# design.net
KiCad netlist of a schematic drawn in Altium Designer
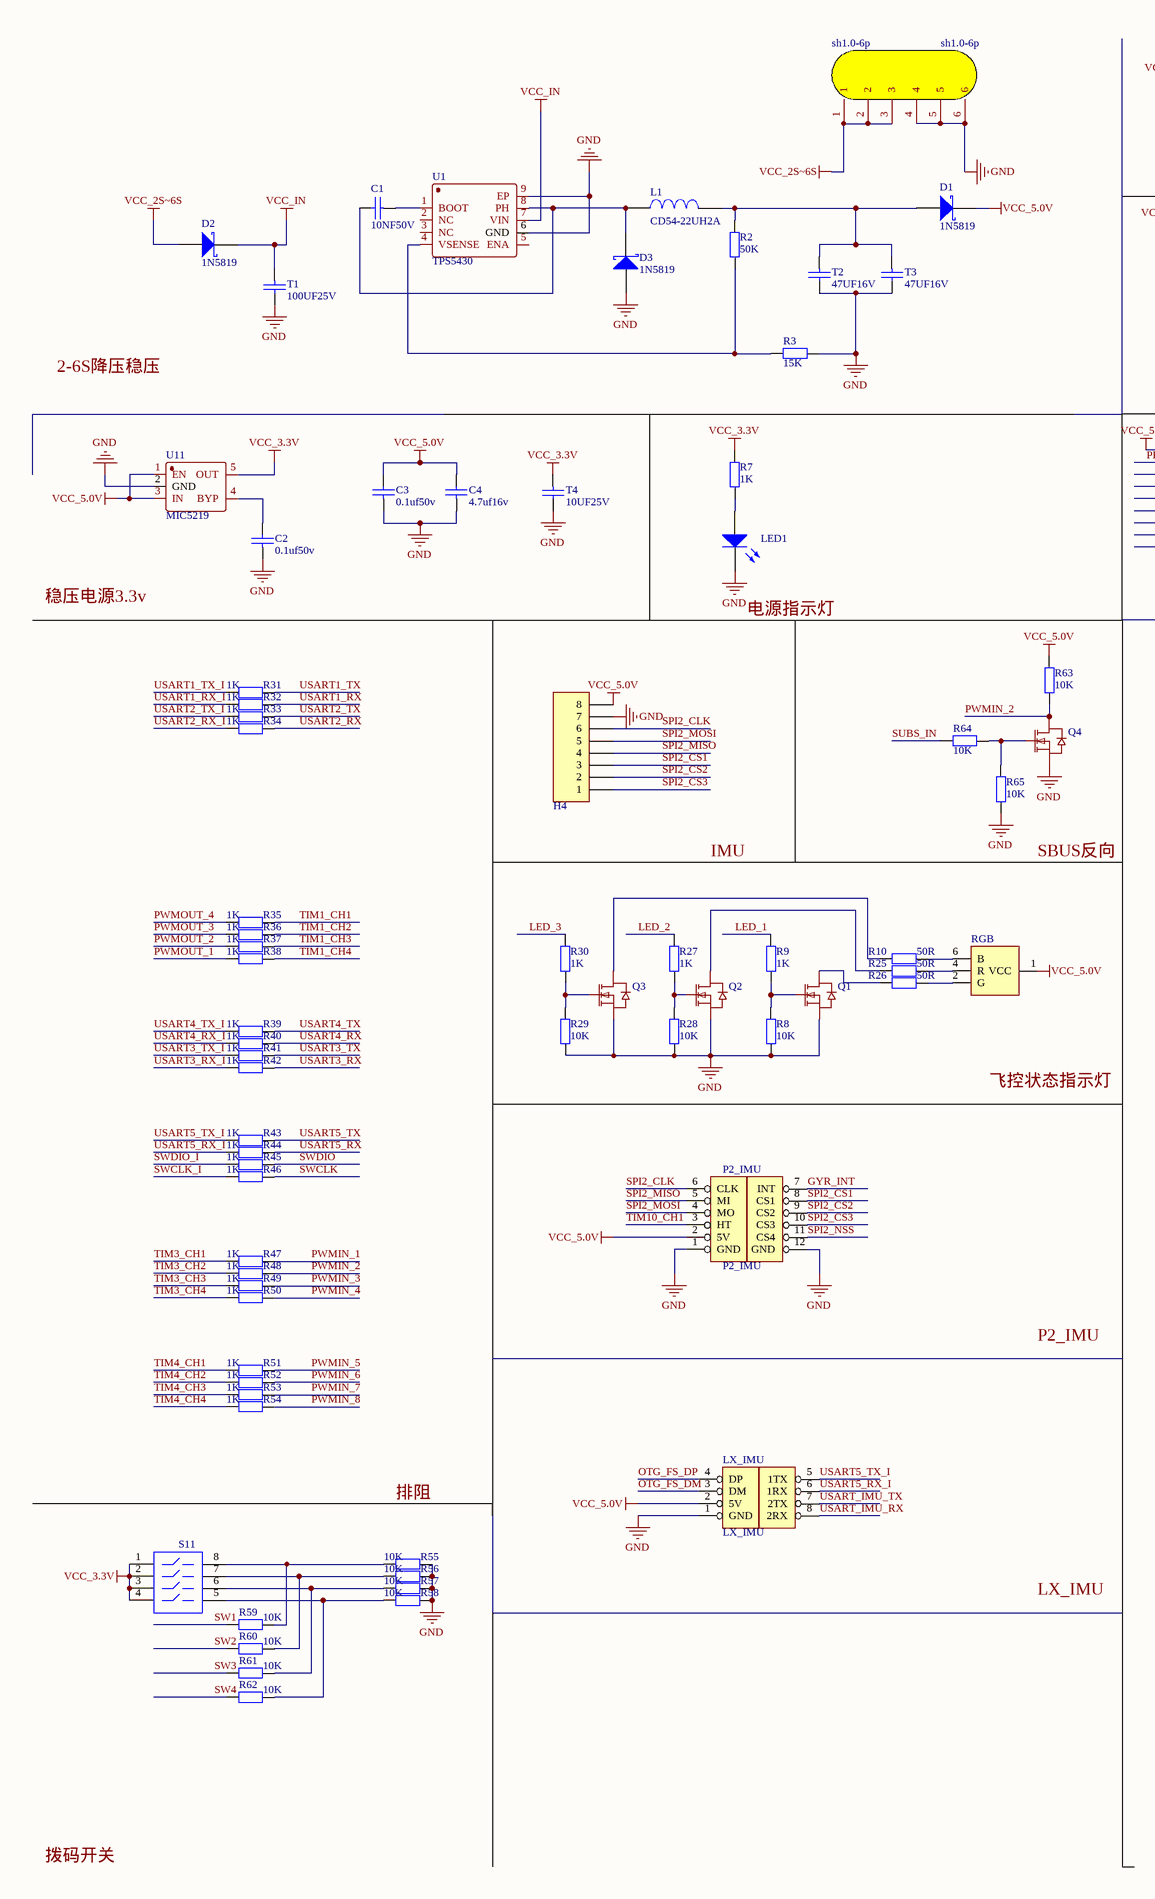
[diagram p0: 飞控板.SchDoc, left]
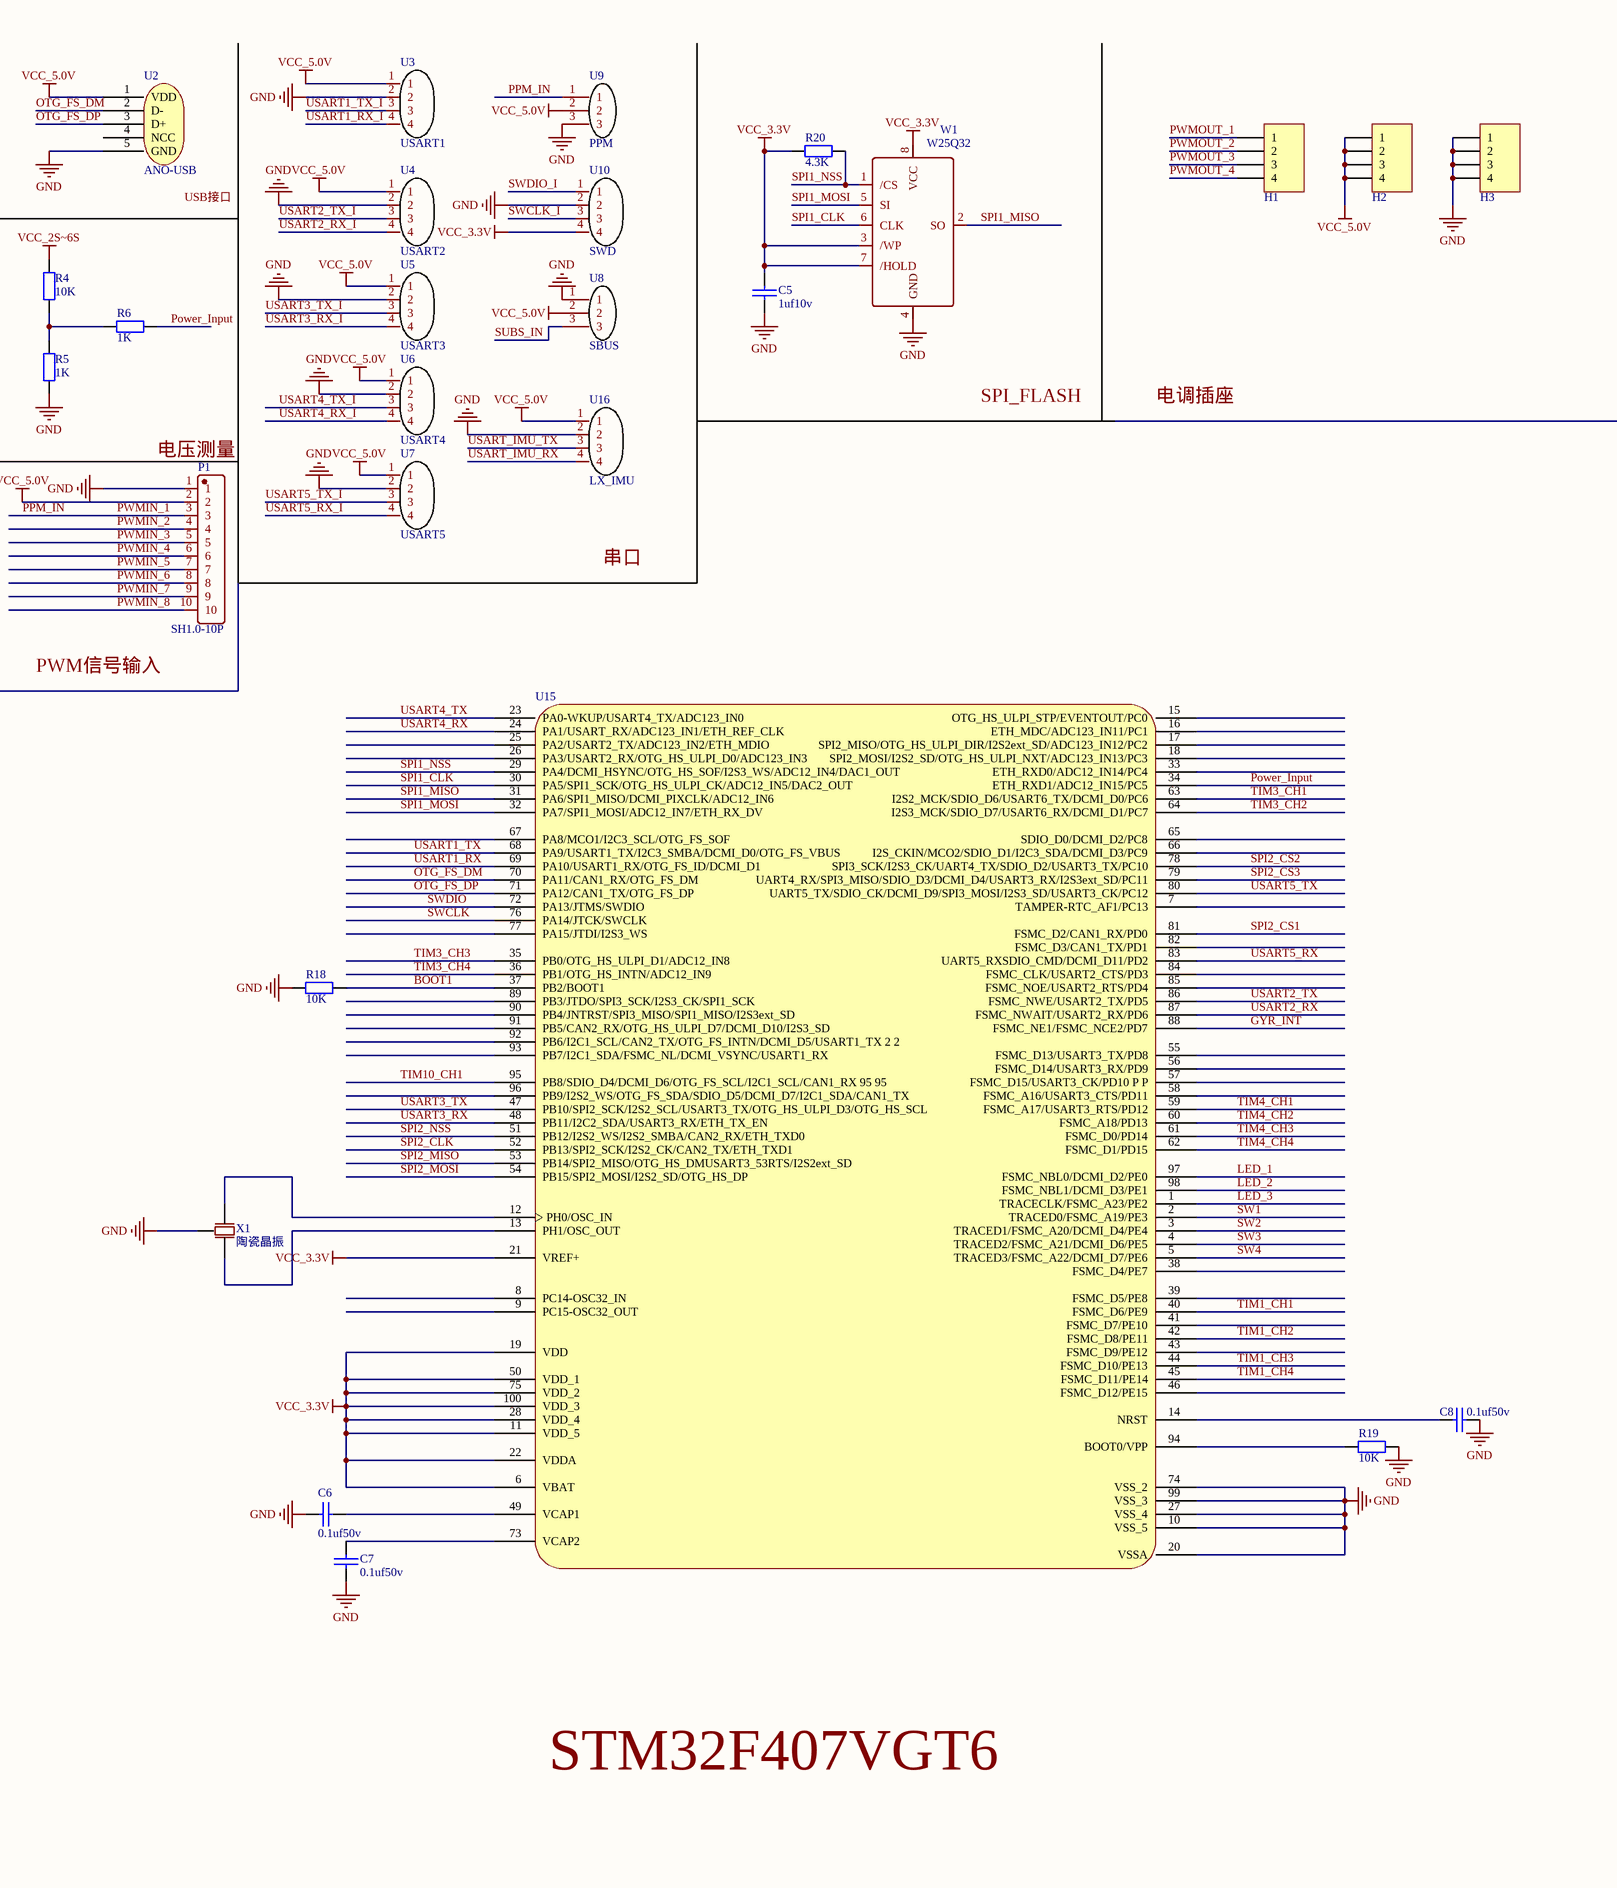
[diagram p1: 飞控板.SchDoc, right]

(export (version "E")
  (design (tool "Eeschema 10.0.6"))
  (components
    (comp (ref "C1")
      (value "10NF50V")
      (footprint "0805C")
      (description "无极性电容")
      (libsource (lib "电容") (part "CAP"))
    )
    (comp (ref "C2")
      (value "0.1uf50v")
      (footprint "0805C")
      (description "无极性电容")
      (libsource (lib "电容") (part "CAP"))
    )
    (comp (ref "C3")
      (value "0.1uf50v")
      (footprint "0805C")
      (description "无极性电容")
      (libsource (lib "电容") (part "CAP"))
    )
    (comp (ref "C4")
      (value "4.7uf16v")
      (footprint "0805C")
      (description "无极性电容")
      (libsource (lib "电容") (part "CAP"))
    )
    (comp (ref "C5")
      (value "1uf10v")
      (footprint "0805C")
      (description "无极性电容")
      (libsource (lib "电容") (part "CAP"))
    )
    (comp (ref "C6")
      (value "0.1uf50v")
      (footprint "0805C")
      (description "无极性电容")
      (libsource (lib "电容") (part "CAP"))
    )
    (comp (ref "C7")
      (value "0.1uf50v")
      (footprint "0805C")
      (description "无极性电容")
      (libsource (lib "电容") (part "CAP"))
    )
    (comp (ref "C8")
      (value "0.1uf50v")
      (footprint "0805C")
      (description "无极性电容")
      (libsource (lib "电容") (part "CAP"))
    )
    (comp (ref "D1")
      (value "1N5819")
      (footprint "DO214AC_SMA")
      (description "贴片肖特基二极管")
      (libsource (lib "1.二极管") (part "1N5817-5819SMD"))
    )
    (comp (ref "D2")
      (value "1N5819")
      (footprint "DO214AC_SMA")
      (description "贴片肖特基二极管")
      (libsource (lib "1.二极管") (part "1N5817-5819SMD"))
    )
    (comp (ref "D3")
      (value "1N5819")
      (footprint "DO214AC_SMA")
      (description "贴片肖特基二极管")
      (libsource (lib "1.二极管") (part "1N5817-5819SMD"))
    )
    (comp (ref "H1")
      (value "Header 4")
      (footprint "HDR1X4")
      (description "Header, 4-Pin")
      (fields (field (name "PUBLISHER") "Altium Limited"))
      (libsource (lib "9.接插件 连接器") (part "Header 4"))
    )
    (comp (ref "H2")
      (value "Header 4")
      (footprint "HDR1X4")
      (description "Header, 4-Pin")
      (fields (field (name "PUBLISHER") "Altium Limited"))
      (libsource (lib "9.接插件 连接器") (part "Header 4"))
    )
    (comp (ref "H3")
      (value "Header 4")
      (footprint "HDR1X4")
      (description "Header, 4-Pin")
      (fields (field (name "PUBLISHER") "Altium Limited"))
      (libsource (lib "9.接插件 连接器") (part "Header 4"))
    )
    (comp (ref "H4")
      (value "Header 8")
      (footprint "HDR1X8")
      (description "Header, 8-Pin")
      (fields (field (name "PUBLISHER") "Altium Limited"))
      (libsource (lib "9.接插件 连接器") (part "Header 8"))
    )
    (comp (ref "L1")
      (value "CD54-22UH2A")
      (footprint "CDRH73")
      (description "INDUCTOR")
      (libsource (lib "电感") (part "INDUCTOR"))
    )
    (comp (ref "LED1") (value "~") (footprint "LED-1206") (libsource (lib "1.二极管") (part "LED1206")))
    (comp (ref "LX_IMU") (value "LX_IMU") (footprint "LX_IMU") (libsource (lib "LX_IMU") (part "LX_IMU")))
    (comp (ref "P1")
      (value "SH1.0-10P")
      (footprint "SH1.0-10P")
      (libsource (lib "SH1.0-10P") (part "SH1.0-10P"))
    )
    (comp (ref "P2_IMU")
      (value "P2_IMU")
      (footprint "P2_IMU")
      (libsource (lib "P2_IMU") (part "Component_1"))
    )
    (comp (ref "Q1") (value "~") (footprint "SI2310") (libsource (lib "SI2310") (part "SI2310")))
    (comp (ref "Q2") (value "~") (footprint "SI2310") (libsource (lib "SI2310") (part "SI2310")))
    (comp (ref "Q3") (value "~") (footprint "SI2310") (libsource (lib "SI2310") (part "SI2310")))
    (comp (ref "Q4") (value "~") (footprint "SI2310") (libsource (lib "SI2310") (part "SI2310")))
    (comp (ref "R2")
      (value "50K")
      (footprint "0805R")
      (description "0805贴片电阻")
      (libsource (lib "") (part "Res_0805_1"))
    )
    (comp (ref "R3")
      (value "15K")
      (footprint "0805R")
      (description "0805贴片电阻")
      (libsource (lib "0.电阻电容电感") (part "Res_0805"))
    )
    (comp (ref "R4")
      (value "10K")
      (footprint "0805R")
      (description "0805贴片电阻")
      (libsource (lib "") (part "Res_0805_1"))
    )
    (comp (ref "R5")
      (value "1K")
      (footprint "0805R")
      (description "0805贴片电阻")
      (libsource (lib "") (part "Res_0805_1"))
    )
    (comp (ref "R6")
      (value "1K")
      (footprint "0805R")
      (description "0805贴片电阻")
      (libsource (lib "0.电阻电容电感") (part "Res_0805"))
    )
    (comp (ref "R7")
      (value "1K")
      (footprint "0805R")
      (description "0805贴片电阻")
      (libsource (lib "") (part "Res_0805_1"))
    )
    (comp (ref "R8")
      (value "10K")
      (footprint "0805R")
      (description "0805贴片电阻")
      (libsource (lib "") (part "Res_0805_1"))
    )
    (comp (ref "R9")
      (value "1K")
      (footprint "0805R")
      (description "0805贴片电阻")
      (libsource (lib "") (part "Res_0805_1"))
    )
    (comp (ref "R10")
      (value "50R")
      (footprint "0805R")
      (description "0805贴片电阻")
      (libsource (lib "") (part "Res_0805_2"))
    )
    (comp (ref "R18")
      (value "10K")
      (footprint "0805R")
      (description "0805贴片电阻")
      (libsource (lib "") (part "Res_0805_2"))
    )
    (comp (ref "R19")
      (value "10K")
      (footprint "0805R")
      (description "0805贴片电阻")
      (libsource (lib "") (part "Res_0805_2"))
    )
    (comp (ref "R20")
      (value "4.3K")
      (footprint "0805R")
      (description "0805贴片电阻")
      (libsource (lib "") (part "Res_0805_2"))
    )
    (comp (ref "R25")
      (value "50R")
      (footprint "0805R")
      (description "0805贴片电阻")
      (libsource (lib "") (part "Res_0805_2"))
    )
    (comp (ref "R26")
      (value "50R")
      (footprint "0805R")
      (description "0805贴片电阻")
      (libsource (lib "") (part "Res_0805_2"))
    )
    (comp (ref "R27")
      (value "1K")
      (footprint "0805R")
      (description "0805贴片电阻")
      (libsource (lib "") (part "Res_0805_1"))
    )
    (comp (ref "R28")
      (value "10K")
      (footprint "0805R")
      (description "0805贴片电阻")
      (libsource (lib "") (part "Res_0805_1"))
    )
    (comp (ref "R29")
      (value "10K")
      (footprint "0805R")
      (description "0805贴片电阻")
      (libsource (lib "") (part "Res_0805_1"))
    )
    (comp (ref "R30")
      (value "1K")
      (footprint "0805R")
      (description "0805贴片电阻")
      (libsource (lib "") (part "Res_0805_1"))
    )
    (comp (ref "R31")
      (value "1K")
      (footprint "0805R")
      (description "0805贴片电阻")
      (libsource (lib "0.电阻电容电感") (part "Res_0805"))
    )
    (comp (ref "R32")
      (value "1K")
      (footprint "0805R")
      (description "0805贴片电阻")
      (libsource (lib "0.电阻电容电感") (part "Res_0805"))
    )
    (comp (ref "R33")
      (value "1K")
      (footprint "0805R")
      (description "0805贴片电阻")
      (libsource (lib "0.电阻电容电感") (part "Res_0805"))
    )
    (comp (ref "R34")
      (value "1K")
      (footprint "0805R")
      (description "0805贴片电阻")
      (libsource (lib "0.电阻电容电感") (part "Res_0805"))
    )
    (comp (ref "R35")
      (value "1K")
      (footprint "0805R")
      (description "0805贴片电阻")
      (libsource (lib "0.电阻电容电感") (part "Res_0805"))
    )
    (comp (ref "R36")
      (value "1K")
      (footprint "0805R")
      (description "0805贴片电阻")
      (libsource (lib "0.电阻电容电感") (part "Res_0805"))
    )
    (comp (ref "R37")
      (value "1K")
      (footprint "0805R")
      (description "0805贴片电阻")
      (libsource (lib "0.电阻电容电感") (part "Res_0805"))
    )
    (comp (ref "R38")
      (value "1K")
      (footprint "0805R")
      (description "0805贴片电阻")
      (libsource (lib "0.电阻电容电感") (part "Res_0805"))
    )
    (comp (ref "R39")
      (value "1K")
      (footprint "0805R")
      (description "0805贴片电阻")
      (libsource (lib "0.电阻电容电感") (part "Res_0805"))
    )
    (comp (ref "R40")
      (value "1K")
      (footprint "0805R")
      (description "0805贴片电阻")
      (libsource (lib "0.电阻电容电感") (part "Res_0805"))
    )
    (comp (ref "R41")
      (value "1K")
      (footprint "0805R")
      (description "0805贴片电阻")
      (libsource (lib "0.电阻电容电感") (part "Res_0805"))
    )
    (comp (ref "R42")
      (value "1K")
      (footprint "0805R")
      (description "0805贴片电阻")
      (libsource (lib "0.电阻电容电感") (part "Res_0805"))
    )
    (comp (ref "R43")
      (value "1K")
      (footprint "0805R")
      (description "0805贴片电阻")
      (libsource (lib "0.电阻电容电感") (part "Res_0805"))
    )
    (comp (ref "R44")
      (value "1K")
      (footprint "0805R")
      (description "0805贴片电阻")
      (libsource (lib "0.电阻电容电感") (part "Res_0805"))
    )
    (comp (ref "R45")
      (value "1K")
      (footprint "0805R")
      (description "0805贴片电阻")
      (libsource (lib "0.电阻电容电感") (part "Res_0805"))
    )
    (comp (ref "R46")
      (value "1K")
      (footprint "0805R")
      (description "0805贴片电阻")
      (libsource (lib "0.电阻电容电感") (part "Res_0805"))
    )
    (comp (ref "R47")
      (value "1K")
      (footprint "0805R")
      (description "0805贴片电阻")
      (libsource (lib "0.电阻电容电感") (part "Res_0805"))
    )
    (comp (ref "R48")
      (value "1K")
      (footprint "0805R")
      (description "0805贴片电阻")
      (libsource (lib "0.电阻电容电感") (part "Res_0805"))
    )
    (comp (ref "R49")
      (value "1K")
      (footprint "0805R")
      (description "0805贴片电阻")
      (libsource (lib "0.电阻电容电感") (part "Res_0805"))
    )
    (comp (ref "R50")
      (value "1K")
      (footprint "0805R")
      (description "0805贴片电阻")
      (libsource (lib "0.电阻电容电感") (part "Res_0805"))
    )
    (comp (ref "R51")
      (value "1K")
      (footprint "0805R")
      (description "0805贴片电阻")
      (libsource (lib "0.电阻电容电感") (part "Res_0805"))
    )
    (comp (ref "R52")
      (value "1K")
      (footprint "0805R")
      (description "0805贴片电阻")
      (libsource (lib "0.电阻电容电感") (part "Res_0805"))
    )
    (comp (ref "R53")
      (value "1K")
      (footprint "0805R")
      (description "0805贴片电阻")
      (libsource (lib "0.电阻电容电感") (part "Res_0805"))
    )
    (comp (ref "R54")
      (value "1K")
      (footprint "0805R")
      (description "0805贴片电阻")
      (libsource (lib "0.电阻电容电感") (part "Res_0805"))
    )
    (comp (ref "R55")
      (value "10K")
      (footprint "0805R")
      (description "0805贴片电阻")
      (libsource (lib "0.电阻电容电感") (part "Res_0805"))
    )
    (comp (ref "R56")
      (value "10K")
      (footprint "0805R")
      (description "0805贴片电阻")
      (libsource (lib "0.电阻电容电感") (part "Res_0805"))
    )
    (comp (ref "R57")
      (value "10K")
      (footprint "0805R")
      (description "0805贴片电阻")
      (libsource (lib "0.电阻电容电感") (part "Res_0805"))
    )
    (comp (ref "R58")
      (value "10K")
      (footprint "0805R")
      (description "0805贴片电阻")
      (libsource (lib "0.电阻电容电感") (part "Res_0805"))
    )
    (comp (ref "R59")
      (value "10K")
      (footprint "0805R")
      (description "0805贴片电阻")
      (libsource (lib "0.电阻电容电感") (part "Res_0805"))
    )
    (comp (ref "R60")
      (value "10K")
      (footprint "0805R")
      (description "0805贴片电阻")
      (libsource (lib "0.电阻电容电感") (part "Res_0805"))
    )
    (comp (ref "R61")
      (value "10K")
      (footprint "0805R")
      (description "0805贴片电阻")
      (libsource (lib "0.电阻电容电感") (part "Res_0805"))
    )
    (comp (ref "R62")
      (value "10K")
      (footprint "0805R")
      (description "0805贴片电阻")
      (libsource (lib "0.电阻电容电感") (part "Res_0805"))
    )
    (comp (ref "R63")
      (value "10K")
      (footprint "0805R")
      (description "0805贴片电阻")
      (libsource (lib "") (part "Res_0805_1"))
    )
    (comp (ref "R64")
      (value "10K")
      (footprint "0805R")
      (description "0805贴片电阻")
      (libsource (lib "0.电阻电容电感") (part "Res_0805"))
    )
    (comp (ref "R65")
      (value "10K")
      (footprint "0805R")
      (description "0805贴片电阻")
      (libsource (lib "") (part "Res_0805_3"))
    )
    (comp (ref "RGB")
      (value "~")
      (footprint "RGB_LED")
      (description "RGB")
      (libsource (lib "RGB灯") (part "RGB"))
    )
    (comp (ref "S11")
      (value "SW-DIP4")
      (footprint "拨码开关4P")
      (description "4P拨码开关")
      (fields (field (name "PUBLISHER") "Altium Limited"))
      (libsource (lib "6.开关 按键") (part "SW-DIP4"))
    )
    (comp (ref "sh1.0-6p")
      (value "sh1.0-6p")
      (footprint "sh1.0-6p")
      (libsource (lib "sh1.0-6p") (part "sh1.0-6p"))
    )
    (comp (ref "T1")
      (value "100UF25V")
      (footprint "0805C")
      (description "无极性电容")
      (libsource (lib "电容") (part "CAP"))
    )
    (comp (ref "T2")
      (value "47UF16V")
      (footprint "0805C")
      (description "无极性电容")
      (libsource (lib "电容") (part "CAP"))
    )
    (comp (ref "T3")
      (value "47UF16V")
      (footprint "0805C")
      (description "无极性电容")
      (libsource (lib "电容") (part "CAP"))
    )
    (comp (ref "T4")
      (value "10UF25V")
      (footprint "0805C")
      (description "无极性电容")
      (libsource (lib "电容") (part "CAP"))
    )
    (comp (ref "U1") (value "TPS5430") (footprint "TPS5430") (libsource (lib "TPS5430") (part "TPS5430")))
    (comp (ref "U2") (value "ANO-USB") (footprint "ANO-USB") (libsource (lib "ANO-USB") (part "ANO-USB")))
    (comp (ref "U3") (value "USART1") (footprint "SH1.0-4P") (libsource (lib "SH1.0-4P") (part "SH1.0-4P")))
    (comp (ref "U4") (value "USART2") (footprint "SH1.0-4P") (libsource (lib "SH1.0-4P") (part "SH1.0-4P")))
    (comp (ref "U5") (value "USART3") (footprint "SH1.0-4P") (libsource (lib "SH1.0-4P") (part "SH1.0-4P")))
    (comp (ref "U6") (value "USART4") (footprint "SH1.0-4P") (libsource (lib "SH1.0-4P") (part "SH1.0-4P")))
    (comp (ref "U7") (value "USART5") (footprint "SH1.0-4P") (libsource (lib "SH1.0-4P") (part "SH1.0-4P")))
    (comp (ref "U8") (value "SBUS") (footprint "SH1.0-3P") (libsource (lib "SH1.0-3P") (part "SH1.0-3P")))
    (comp (ref "U9") (value "PPM") (footprint "SH1.0-3P") (libsource (lib "SH1.0-3P") (part "SH1.0-3P")))
    (comp (ref "U10") (value "SWD") (footprint "SH1.0-4P") (libsource (lib "SH1.0-4P") (part "SH1.0-4P")))
    (comp (ref "U11") (value "MIC5219") (footprint "MIC5219") (libsource (lib "MIC5219") (part "MIC5219")))
    (comp (ref "U15")
      (value "~")
      (footprint "STM32F407VGT6=")
      (libsource (lib "STM32F407VGT6=") (part "STM32F407VGT6="))
    )
    (comp (ref "U16") (value "LX_IMU") (footprint "SH1.0-4P") (libsource (lib "SH1.0-4P") (part "SH1.0-4P")))
    (comp (ref "W1") (value "W25Q32") (footprint "W25Q32") (libsource (lib "W25Q32") (part "W25Q32")))
    (comp (ref "X1") (value "陶瓷晶振") (footprint "陶瓷晶振") (libsource (lib "陶瓷晶振") (part "陶瓷晶振")))
  )
  (nets
    (net (code "2") (name "/BOOT1") (class "Default")
      (node (ref "R18") (pin "1") (pinfunction "1_1") (pintype "passive"))
      (node (ref "U15") (pin "37") (pinfunction "PB2/BOOT1_37") (pintype "passive"))
    )
    (net (code "3") (name "/GYR_INT") (class "Default")
      (node (ref "P2_IMU") (pin "7") (pinfunction "INT_7") (pintype "passive"))
      (node (ref "U15") (pin "88") (pinfunction "FSMC_NE1/FSMC_NCE2/PD7_88") (pintype "passive"))
    )
    (net (code "5") (name "/LED_1") (class "Default")
      (node (ref "R9") (pin "1") (pinfunction "1_1") (pintype "passive"))
      (node (ref "U15") (pin "97") (pinfunction "FSMC_NBL0/DCMI_D2/PE0_97") (pintype "passive"))
    )
    (net (code "6") (name "/LED_2") (class "Default")
      (node (ref "R27") (pin "1") (pinfunction "1_1") (pintype "passive"))
      (node (ref "U15") (pin "98") (pinfunction "FSMC_NBL1/DCMI_D3/PE1_98") (pintype "passive"))
    )
    (net (code "7") (name "/LED_3") (class "Default")
      (node (ref "R30") (pin "1") (pinfunction "1_1") (pintype "passive"))
      (node (ref "U15") (pin "1") (pinfunction "TRACECLK/FSMC_A23/PE2_1") (pintype "passive"))
    )
    (net (code "9") (name "/OTG_FS_DM") (class "Default")
      (node (ref "LX_IMU") (pin "3") (pinfunction "DM_3") (pintype "passive"))
      (node (ref "U15") (pin "70") (pinfunction "PA11/CAN1_RX/OTG_FS_DM_70") (pintype "passive"))
      (node (ref "U2") (pin "2") (pinfunction "D-_2") (pintype "passive"))
    )
    (net (code "10") (name "/OTG_FS_DP") (class "Default")
      (node (ref "LX_IMU") (pin "4") (pinfunction "DP_4") (pintype "passive"))
      (node (ref "U15") (pin "71") (pinfunction "PA12/CAN1_TX/OTG_FS_DP_71") (pintype "passive"))
      (node (ref "U2") (pin "3") (pinfunction "D+_3") (pintype "passive"))
    )
    (net (code "12") (name "/PPM_IN") (class "Default")
      (node (ref "P1") (pin "3") (pinfunction "3_3") (pintype "passive"))
      (node (ref "R47") (pin "2") (pinfunction "2_2") (pintype "passive"))
      (node (ref "U9") (pin "1") (pinfunction "1_1") (pintype "passive"))
    )
    (net (code "13") (name "/PWMIN_2") (class "Default")
      (node (ref "P1") (pin "4") (pinfunction "4_4") (pintype "passive"))
      (node (ref "Q4") (pin "3") (pinfunction "D_3") (pintype "passive"))
      (node (ref "R48") (pin "2") (pinfunction "2_2") (pintype "passive"))
      (node (ref "R63") (pin "2") (pinfunction "2_2") (pintype "passive"))
    )
    (net (code "14") (name "/PWMIN_3") (class "Default")
      (node (ref "P1") (pin "5") (pinfunction "5_5") (pintype "passive"))
      (node (ref "R49") (pin "2") (pinfunction "2_2") (pintype "passive"))
    )
    (net (code "15") (name "/PWMIN_4") (class "Default")
      (node (ref "P1") (pin "6") (pinfunction "6_6") (pintype "passive"))
      (node (ref "R50") (pin "2") (pinfunction "2_2") (pintype "passive"))
    )
    (net (code "16") (name "/PWMIN_5") (class "Default")
      (node (ref "P1") (pin "7") (pinfunction "7_7") (pintype "passive"))
      (node (ref "R51") (pin "2") (pinfunction "2_2") (pintype "passive"))
    )
    (net (code "17") (name "/PWMIN_6") (class "Default")
      (node (ref "P1") (pin "8") (pinfunction "8_8") (pintype "passive"))
      (node (ref "R52") (pin "2") (pinfunction "2_2") (pintype "passive"))
    )
    (net (code "18") (name "/PWMIN_7") (class "Default")
      (node (ref "P1") (pin "9") (pinfunction "9_9") (pintype "passive"))
      (node (ref "R53") (pin "2") (pinfunction "2_2") (pintype "passive"))
    )
    (net (code "19") (name "/PWMIN_8") (class "Default")
      (node (ref "P1") (pin "10") (pinfunction "10_10") (pintype "passive"))
      (node (ref "R54") (pin "2") (pinfunction "2_2") (pintype "passive"))
    )
    (net (code "20") (name "/PWMOUT_1") (class "Default")
      (node (ref "H1") (pin "1") (pinfunction "1_1") (pintype "passive"))
      (node (ref "R38") (pin "1") (pinfunction "1_1") (pintype "passive"))
    )
    (net (code "21") (name "/PWMOUT_2") (class "Default")
      (node (ref "H1") (pin "2") (pinfunction "2_2") (pintype "passive"))
      (node (ref "R37") (pin "1") (pinfunction "1_1") (pintype "passive"))
    )
    (net (code "22") (name "/PWMOUT_3") (class "Default")
      (node (ref "H1") (pin "3") (pinfunction "3_3") (pintype "passive"))
      (node (ref "R36") (pin "1") (pinfunction "1_1") (pintype "passive"))
    )
    (net (code "23") (name "/PWMOUT_4") (class "Default")
      (node (ref "H1") (pin "4") (pinfunction "4_4") (pintype "passive"))
      (node (ref "R35") (pin "1") (pinfunction "1_1") (pintype "passive"))
    )
    (net (code "25") (name "/Power_Input") (class "Default")
      (node (ref "R6") (pin "2") (pinfunction "2_2") (pintype "passive"))
      (node (ref "U15") (pin "34") (pinfunction "ETH_RXD1/ADC12_IN15/PC5_34") (pintype "passive"))
    )
    (net (code "27") (name "/SPI1_CLK") (class "Default")
      (node (ref "U15") (pin "30") (pinfunction "PA5/SPI1_SCK/OTG_HS_ULPI_CK/ADC12_IN5/DAC2_OUT_30") (pintype "passive"))
      (node (ref "W1") (pin "6") (pinfunction "CLK_6") (pintype "passive"))
    )
    (net (code "28") (name "/SPI1_MISO") (class "Default")
      (node (ref "U15") (pin "31") (pinfunction "PA6/SPI1_MISO/DCMI_PIXCLK/ADC12_IN6_31") (pintype "passive"))
      (node (ref "W1") (pin "2") (pinfunction "SO_2") (pintype "passive"))
    )
    (net (code "29") (name "/SPI1_MOSI") (class "Default")
      (node (ref "U15") (pin "32") (pinfunction "PA7/SPI1_MOSI/ADC12_IN7/ETH_RX_DV_32") (pintype "passive"))
      (node (ref "W1") (pin "5") (pinfunction "SI_5") (pintype "passive"))
    )
    (net (code "30") (name "/SPI1_NSS") (class "Default")
      (node (ref "R20") (pin "1") (pinfunction "1_1") (pintype "passive"))
      (node (ref "U15") (pin "29") (pinfunction "PA4/DCMI_HSYNC/OTG_HS_SOF/I2S3_WS/ADC12_IN4/DAC1_OUT_29") (pintype "passive"))
      (node (ref "W1") (pin "1") (pinfunction "/CS_1") (pintype "passive"))
    )
    (net (code "31") (name "/SPI2_CLK") (class "Default")
      (node (ref "H4") (pin "6") (pinfunction "6_6") (pintype "passive"))
      (node (ref "P2_IMU") (pin "6") (pinfunction "CLK_6") (pintype "passive"))
      (node (ref "U15") (pin "52") (pinfunction "PB13/SPI2_SCK/I2S2_CK/CAN2_TX/ETH_TXD1_52") (pintype "passive"))
    )
    (net (code "32") (name "/SPI2_CS1") (class "Default")
      (node (ref "H4") (pin "3") (pinfunction "3_3") (pintype "passive"))
      (node (ref "P2_IMU") (pin "8") (pinfunction "CS1_8") (pintype "passive"))
      (node (ref "U15") (pin "81") (pinfunction "FSMC_D2/CAN1_RX/PD0_81") (pintype "passive"))
    )
    (net (code "33") (name "/SPI2_CS2") (class "Default")
      (node (ref "H4") (pin "2") (pinfunction "2_2") (pintype "passive"))
      (node (ref "P2_IMU") (pin "9") (pinfunction "CS2_9") (pintype "passive"))
      (node (ref "U15") (pin "78") (pinfunction "SPI3_SCK/I2S3_CK/UART4_TX/SDIO_D2/USART3_TX/PC10_78") (pintype "passive"))
    )
    (net (code "34") (name "/SPI2_CS3") (class "Default")
      (node (ref "H4") (pin "1") (pinfunction "1_1") (pintype "passive"))
      (node (ref "P2_IMU") (pin "10") (pinfunction "CS3_10") (pintype "passive"))
      (node (ref "U15") (pin "79") (pinfunction "UART4_RX/SPI3_MISO/SDIO_D3/DCMI_D4/USART3_RX/I2S3ext_SD/PC11_79") (pintype "passive"))
    )
    (net (code "35") (name "/SPI2_MISO") (class "Default")
      (node (ref "H4") (pin "4") (pinfunction "4_4") (pintype "passive"))
      (node (ref "P2_IMU") (pin "5") (pinfunction "MI_5") (pintype "passive"))
      (node (ref "U15") (pin "53") (pinfunction "PB14/SPI2_MISO/OTG_HS_DMUSART3_53RTS/I2S2ext_SD_53") (pintype "passive"))
    )
    (net (code "36") (name "/SPI2_MOSI") (class "Default")
      (node (ref "H4") (pin "5") (pinfunction "5_5") (pintype "passive"))
      (node (ref "P2_IMU") (pin "4") (pinfunction "MO_4") (pintype "passive"))
      (node (ref "U15") (pin "54") (pinfunction "PB15/SPI2_MOSI/I2S2_SD/OTG_HS_DP_54") (pintype "passive"))
    )
    (net (code "37") (name "/SPI2_NSS") (class "Default")
      (node (ref "P2_IMU") (pin "11") (pinfunction "CS4_11") (pintype "passive"))
      (node (ref "U15") (pin "51") (pinfunction "PB12/I2S2_WS/I2S2_SMBA/CAN2_RX/ETH_TXD0_51") (pintype "passive"))
    )
    (net (code "40") (name "/SUBS_IN") (class "Default")
      (node (ref "R64") (pin "1") (pinfunction "1_1") (pintype "passive"))
      (node (ref "U8") (pin "3") (pinfunction "3_3") (pintype "passive"))
    )
    (net (code "41") (name "/SW1") (class "Default")
      (node (ref "R59") (pin "1") (pinfunction "1_1") (pintype "passive"))
      (node (ref "U15") (pin "2") (pinfunction "TRACED0/FSMC_A19/PE3_2") (pintype "passive"))
    )
    (net (code "42") (name "/SW2") (class "Default")
      (node (ref "R60") (pin "1") (pinfunction "1_1") (pintype "passive"))
      (node (ref "U15") (pin "3") (pinfunction "TRACED1/FSMC_A20/DCMI_D4/PE4_3") (pintype "passive"))
    )
    (net (code "43") (name "/SW3") (class "Default")
      (node (ref "R61") (pin "1") (pinfunction "1_1") (pintype "passive"))
      (node (ref "U15") (pin "4") (pinfunction "TRACED2/FSMC_A21/DCMI_D6/PE5_4") (pintype "passive"))
    )
    (net (code "44") (name "/SW4") (class "Default")
      (node (ref "R62") (pin "1") (pinfunction "1_1") (pintype "passive"))
      (node (ref "U15") (pin "5") (pinfunction "TRACED3/FSMC_A22/DCMI_D7/PE6_5") (pintype "passive"))
    )
    (net (code "45") (name "/SWCLK") (class "Default")
      (node (ref "R46") (pin "2") (pinfunction "2_2") (pintype "passive"))
      (node (ref "U15") (pin "76") (pinfunction "PA14/JTCK/SWCLK_76") (pintype "passive"))
    )
    (net (code "46") (name "/SWCLK_I") (class "Default")
      (node (ref "R46") (pin "1") (pinfunction "1_1") (pintype "passive"))
      (node (ref "U10") (pin "3") (pinfunction "3_3") (pintype "passive"))
    )
    (net (code "47") (name "/SWDIO") (class "Default")
      (node (ref "R45") (pin "2") (pinfunction "2_2") (pintype "passive"))
      (node (ref "U15") (pin "72") (pinfunction "PA13/JTMS/SWDIO_72") (pintype "passive"))
    )
    (net (code "48") (name "/SWDIO_I") (class "Default")
      (node (ref "R45") (pin "1") (pinfunction "1_1") (pintype "passive"))
      (node (ref "U10") (pin "1") (pinfunction "1_1") (pintype "passive"))
    )
    (net (code "49") (name "/TIM1_CH1") (class "Default")
      (node (ref "R35") (pin "2") (pinfunction "2_2") (pintype "passive"))
      (node (ref "U15") (pin "40") (pinfunction "FSMC_D6/PE9_40") (pintype "passive"))
    )
    (net (code "50") (name "/TIM1_CH2") (class "Default")
      (node (ref "R36") (pin "2") (pinfunction "2_2") (pintype "passive"))
      (node (ref "U15") (pin "42") (pinfunction "FSMC_D8/PE11_42") (pintype "passive"))
    )
    (net (code "51") (name "/TIM1_CH3") (class "Default")
      (node (ref "R37") (pin "2") (pinfunction "2_2") (pintype "passive"))
      (node (ref "U15") (pin "44") (pinfunction "FSMC_D10/PE13_44") (pintype "passive"))
    )
    (net (code "52") (name "/TIM1_CH4") (class "Default")
      (node (ref "R38") (pin "2") (pinfunction "2_2") (pintype "passive"))
      (node (ref "U15") (pin "45") (pinfunction "FSMC_D11/PE14_45") (pintype "passive"))
    )
    (net (code "53") (name "/TIM3_CH1") (class "Default")
      (node (ref "R47") (pin "1") (pinfunction "1_1") (pintype "passive"))
      (node (ref "U15") (pin "63") (pinfunction "I2S2_MCK/SDIO_D6/USART6_TX/DCMI_D0/PC6_63") (pintype "passive"))
    )
    (net (code "54") (name "/TIM3_CH2") (class "Default")
      (node (ref "R48") (pin "1") (pinfunction "1_1") (pintype "passive"))
      (node (ref "U15") (pin "64") (pinfunction "I2S3_MCK/SDIO_D7/USART6_RX/DCMI_D1/PC7_64") (pintype "passive"))
    )
    (net (code "55") (name "/TIM3_CH3") (class "Default")
      (node (ref "R49") (pin "1") (pinfunction "1_1") (pintype "passive"))
      (node (ref "U15") (pin "35") (pinfunction "PB0/OTG_HS_ULPI_D1/ADC12_IN8_35") (pintype "passive"))
    )
    (net (code "56") (name "/TIM3_CH4") (class "Default")
      (node (ref "R50") (pin "1") (pinfunction "1_1") (pintype "passive"))
      (node (ref "U15") (pin "36") (pinfunction "PB1/OTG_HS_INTN/ADC12_IN9_36") (pintype "passive"))
    )
    (net (code "57") (name "/TIM4_CH1") (class "Default")
      (node (ref "R51") (pin "1") (pinfunction "1_1") (pintype "passive"))
      (node (ref "U15") (pin "59") (pinfunction "FSMC_A17/USART3_RTS/PD12_59") (pintype "passive"))
    )
    (net (code "58") (name "/TIM4_CH2") (class "Default")
      (node (ref "R52") (pin "1") (pinfunction "1_1") (pintype "passive"))
      (node (ref "U15") (pin "60") (pinfunction "FSMC_A18/PD13_60") (pintype "passive"))
    )
    (net (code "59") (name "/TIM4_CH3") (class "Default")
      (node (ref "R53") (pin "1") (pinfunction "1_1") (pintype "passive"))
      (node (ref "U15") (pin "61") (pinfunction "FSMC_D0/PD14_61") (pintype "passive"))
    )
    (net (code "60") (name "/TIM4_CH4") (class "Default")
      (node (ref "R54") (pin "1") (pinfunction "1_1") (pintype "passive"))
      (node (ref "U15") (pin "62") (pinfunction "FSMC_D1/PD15_62") (pintype "passive"))
    )
    (net (code "61") (name "/TIM10_CH1") (class "Default")
      (node (ref "P2_IMU") (pin "3") (pinfunction "HT_3") (pintype "passive"))
      (node (ref "U15") (pin "95") (pinfunction "PB8/SDIO_D4/DCMI_D6/OTG_FS_SCL/I2C1_SCL/CAN1_RX_95_95_95") (pintype "passive"))
    )
    (net (code "62") (name "/USART1_RX") (class "Default")
      (node (ref "R32") (pin "2") (pinfunction "2_2") (pintype "passive"))
      (node (ref "U15") (pin "69") (pinfunction "PA10/USART1_RX/OTG_FS_ID/DCMI_D1_69") (pintype "passive"))
    )
    (net (code "63") (name "/USART1_RX_I") (class "Default")
      (node (ref "R32") (pin "1") (pinfunction "1_1") (pintype "passive"))
      (node (ref "U3") (pin "4") (pinfunction "4_4") (pintype "passive"))
    )
    (net (code "64") (name "/USART1_TX") (class "Default")
      (node (ref "R31") (pin "2") (pinfunction "2_2") (pintype "passive"))
      (node (ref "U15") (pin "68") (pinfunction "PA9/USART1_TX/I2C3_SMBA/DCMI_D0/OTG_FS_VBUS_68") (pintype "passive"))
    )
    (net (code "65") (name "/USART1_TX_I") (class "Default")
      (node (ref "R31") (pin "1") (pinfunction "1_1") (pintype "passive"))
      (node (ref "U3") (pin "3") (pinfunction "3_3") (pintype "passive"))
    )
    (net (code "66") (name "/USART2_RX") (class "Default")
      (node (ref "R34") (pin "2") (pinfunction "2_2") (pintype "passive"))
      (node (ref "U15") (pin "87") (pinfunction "FSMC_NWAIT/USART2_RX/PD6_87") (pintype "passive"))
    )
    (net (code "67") (name "/USART2_RX_I") (class "Default")
      (node (ref "R34") (pin "1") (pinfunction "1_1") (pintype "passive"))
      (node (ref "U4") (pin "4") (pinfunction "4_4") (pintype "passive"))
    )
    (net (code "68") (name "/USART2_TX") (class "Default")
      (node (ref "R33") (pin "2") (pinfunction "2_2") (pintype "passive"))
      (node (ref "U15") (pin "86") (pinfunction "FSMC_NWE/USART2_TX/PD5_86") (pintype "passive"))
    )
    (net (code "69") (name "/USART2_TX_I") (class "Default")
      (node (ref "R33") (pin "1") (pinfunction "1_1") (pintype "passive"))
      (node (ref "U4") (pin "3") (pinfunction "3_3") (pintype "passive"))
    )
    (net (code "70") (name "/USART3_RX") (class "Default")
      (node (ref "R42") (pin "2") (pinfunction "2_2") (pintype "passive"))
      (node (ref "U15") (pin "48") (pinfunction "PB11/I2C2_SDA/USART3_RX/ETH_TX_EN_48") (pintype "passive"))
    )
    (net (code "71") (name "/USART3_RX_I") (class "Default")
      (node (ref "R42") (pin "1") (pinfunction "1_1") (pintype "passive"))
      (node (ref "U5") (pin "4") (pinfunction "4_4") (pintype "passive"))
    )
    (net (code "72") (name "/USART3_TX") (class "Default")
      (node (ref "R41") (pin "2") (pinfunction "2_2") (pintype "passive"))
      (node (ref "U15") (pin "47") (pinfunction "PB10/SPI2_SCK/I2S2_SCL/USART3_TX/OTG_HS_ULPI_D3/OTG_HS_SCL_47") (pintype "passive"))
    )
    (net (code "73") (name "/USART3_TX_I") (class "Default")
      (node (ref "R41") (pin "1") (pinfunction "1_1") (pintype "passive"))
      (node (ref "U5") (pin "3") (pinfunction "3_3") (pintype "passive"))
    )
    (net (code "74") (name "/USART4_RX") (class "Default")
      (node (ref "R40") (pin "2") (pinfunction "2_2") (pintype "passive"))
      (node (ref "U15") (pin "24") (pinfunction "PA1/USART_RX/ADC123_IN1/ETH_REF_CLK_24") (pintype "passive"))
    )
    (net (code "75") (name "/USART4_RX_I") (class "Default")
      (node (ref "R40") (pin "1") (pinfunction "1_1") (pintype "passive"))
      (node (ref "U6") (pin "4") (pinfunction "4_4") (pintype "passive"))
    )
    (net (code "76") (name "/USART4_TX") (class "Default")
      (node (ref "R39") (pin "2") (pinfunction "2_2") (pintype "passive"))
      (node (ref "U15") (pin "23") (pinfunction "PA0-WKUP/USART4_TX/ADC123_IN0_23") (pintype "passive"))
    )
    (net (code "77") (name "/USART4_TX_I") (class "Default")
      (node (ref "R39") (pin "1") (pinfunction "1_1") (pintype "passive"))
      (node (ref "U6") (pin "3") (pinfunction "3_3") (pintype "passive"))
    )
    (net (code "78") (name "/USART5_RX") (class "Default")
      (node (ref "R44") (pin "2") (pinfunction "2_2") (pintype "passive"))
      (node (ref "U15") (pin "83") (pinfunction "UART5_RXSDIO_CMD/DCMI_D11/PD2_83") (pintype "passive"))
    )
    (net (code "79") (name "/USART5_RX_I") (class "Default")
      (node (ref "LX_IMU") (pin "6") (pinfunction "1RX_6") (pintype "passive"))
      (node (ref "R44") (pin "1") (pinfunction "1_1") (pintype "passive"))
      (node (ref "U7") (pin "4") (pinfunction "4_4") (pintype "passive"))
    )
    (net (code "80") (name "/USART5_TX") (class "Default")
      (node (ref "R43") (pin "2") (pinfunction "2_2") (pintype "passive"))
      (node (ref "U15") (pin "80") (pinfunction "UART5_TX/SDIO_CK/DCMI_D9/SPI3_MOSI/I2S3_SD/USART3_CK/PC12_80") (pintype "passive"))
    )
    (net (code "81") (name "/USART5_TX_I") (class "Default")
      (node (ref "LX_IMU") (pin "5") (pinfunction "1TX_5") (pintype "passive"))
      (node (ref "R43") (pin "1") (pinfunction "1_1") (pintype "passive"))
      (node (ref "U7") (pin "3") (pinfunction "3_3") (pintype "passive"))
    )
    (net (code "82") (name "/USART_IMU_RX") (class "Default")
      (node (ref "LX_IMU") (pin "8") (pinfunction "2RX_8") (pintype "passive"))
      (node (ref "U16") (pin "4") (pinfunction "4_4") (pintype "passive"))
    )
    (net (code "83") (name "/USART_IMU_TX") (class "Default")
      (node (ref "LX_IMU") (pin "7") (pinfunction "2TX_7") (pintype "passive"))
      (node (ref "U16") (pin "3") (pinfunction "3_3") (pintype "passive"))
    )
    (net (code "93") (name "GND") (class "Default")
      (node (ref "C2") (pin "1") (pinfunction "1_1") (pintype "passive"))
      (node (ref "C3") (pin "1") (pinfunction "1_1") (pintype "passive"))
      (node (ref "C4") (pin "1") (pinfunction "1_1") (pintype "passive"))
      (node (ref "C5") (pin "1") (pinfunction "1_1") (pintype "passive"))
      (node (ref "C6") (pin "1") (pinfunction "1_1") (pintype "passive"))
      (node (ref "C7") (pin "1") (pinfunction "1_1") (pintype "passive"))
      (node (ref "C8") (pin "2") (pinfunction "2_2") (pintype "passive"))
      (node (ref "D3") (pin "1") (pinfunction "A_1") (pintype "passive"))
      (node (ref "H3") (pin "1") (pinfunction "1_1") (pintype "passive"))
      (node (ref "H3") (pin "2") (pinfunction "2_2") (pintype "passive"))
      (node (ref "H3") (pin "3") (pinfunction "3_3") (pintype "passive"))
      (node (ref "H3") (pin "4") (pinfunction "4_4") (pintype "passive"))
      (node (ref "H4") (pin "7") (pinfunction "7_7") (pintype "passive"))
      (node (ref "LED1") (pin "2") (pinfunction "K_2") (pintype "passive"))
      (node (ref "LX_IMU") (pin "1") (pinfunction "GND_1") (pintype "passive"))
      (node (ref "P1") (pin "1") (pinfunction "1_1") (pintype "passive"))
      (node (ref "P2_IMU") (pin "1") (pinfunction "GND_1") (pintype "passive"))
      (node (ref "P2_IMU") (pin "12") (pinfunction "GND_12") (pintype "passive"))
      (node (ref "Q1") (pin "2") (pinfunction "S_2") (pintype "passive"))
      (node (ref "Q2") (pin "2") (pinfunction "S_2") (pintype "passive"))
      (node (ref "Q3") (pin "2") (pinfunction "S_2") (pintype "passive"))
      (node (ref "Q4") (pin "2") (pinfunction "S_2") (pintype "passive"))
      (node (ref "R18") (pin "2") (pinfunction "2_2") (pintype "passive"))
      (node (ref "R19") (pin "1") (pinfunction "1_1") (pintype "passive"))
      (node (ref "R28") (pin "2") (pinfunction "2_2") (pintype "passive"))
      (node (ref "R29") (pin "2") (pinfunction "2_2") (pintype "passive"))
      (node (ref "R3") (pin "2") (pinfunction "2_2") (pintype "passive"))
      (node (ref "R5") (pin "2") (pinfunction "2_2") (pintype "passive"))
      (node (ref "R55") (pin "2") (pinfunction "2_2") (pintype "passive"))
      (node (ref "R56") (pin "2") (pinfunction "2_2") (pintype "passive"))
      (node (ref "R57") (pin "2") (pinfunction "2_2") (pintype "passive"))
      (node (ref "R58") (pin "2") (pinfunction "2_2") (pintype "passive"))
      (node (ref "R65") (pin "1") (pinfunction "1_1") (pintype "passive"))
      (node (ref "R8") (pin "2") (pinfunction "2_2") (pintype "passive"))
      (node (ref "T1") (pin "2") (pinfunction "2_2") (pintype "passive"))
      (node (ref "T2") (pin "2") (pinfunction "2_2") (pintype "passive"))
      (node (ref "T3") (pin "2") (pinfunction "2_2") (pintype "passive"))
      (node (ref "T4") (pin "2") (pinfunction "2_2") (pintype "passive"))
      (node (ref "U1") (pin "6") (pinfunction "GND_6") (pintype "passive"))
      (node (ref "U1") (pin "9") (pinfunction "EP_9") (pintype "passive"))
      (node (ref "U10") (pin "2") (pinfunction "2_2") (pintype "passive"))
      (node (ref "U11") (pin "2") (pinfunction "GND_2") (pintype "passive"))
      (node (ref "U15") (pin "10") (pinfunction "VSS_5_10") (pintype "passive"))
      (node (ref "U15") (pin "20") (pinfunction "VSSA_20") (pintype "passive"))
      (node (ref "U15") (pin "27") (pinfunction "VSS_4_27") (pintype "passive"))
      (node (ref "U15") (pin "74") (pinfunction "VSS_2_74") (pintype "passive"))
      (node (ref "U15") (pin "99") (pinfunction "VSS_3_99") (pintype "passive"))
      (node (ref "U16") (pin "2") (pinfunction "2_2") (pintype "passive"))
      (node (ref "U2") (pin "5") (pinfunction "GND_5") (pintype "passive"))
      (node (ref "U3") (pin "2") (pinfunction "2_2") (pintype "passive"))
      (node (ref "U4") (pin "2") (pinfunction "2_2") (pintype "passive"))
      (node (ref "U5") (pin "2") (pinfunction "2_2") (pintype "passive"))
      (node (ref "U6") (pin "2") (pinfunction "2_2") (pintype "passive"))
      (node (ref "U7") (pin "2") (pinfunction "2_2") (pintype "passive"))
      (node (ref "U8") (pin "1") (pinfunction "1_1") (pintype "passive"))
      (node (ref "U9") (pin "3") (pinfunction "3_3") (pintype "passive"))
      (node (ref "W1") (pin "4") (pinfunction "GND_4") (pintype "passive"))
      (node (ref "X1") (pin "2") (pinfunction "GND_2") (pintype "passive"))
      (node (ref "sh1.0-6p") (pin "4") (pinfunction "4_4") (pintype "passive"))
      (node (ref "sh1.0-6p") (pin "5") (pinfunction "5_5") (pintype "passive"))
      (node (ref "sh1.0-6p") (pin "6") (pinfunction "6_6") (pintype "passive"))
    )
    (net (code "94") (name "Net-(D1-A)") (class "Default")
      (node (ref "D1") (pin "1") (pinfunction "A_1") (pintype "passive"))
      (node (ref "L1") (pin "2") (pinfunction "2_2") (pintype "passive"))
      (node (ref "R2") (pin "1") (pinfunction "1_1") (pintype "passive"))
      (node (ref "T2") (pin "1") (pinfunction "1_1") (pintype "passive"))
      (node (ref "T3") (pin "1") (pinfunction "1_1") (pintype "passive"))
    )
    (net (code "95") (name "Net-(D3-K)") (class "Default")
      (node (ref "C1") (pin "2") (pinfunction "2_2") (pintype "passive"))
      (node (ref "D3") (pin "2") (pinfunction "K_2") (pintype "passive"))
      (node (ref "L1") (pin "1") (pinfunction "1_1") (pintype "passive"))
      (node (ref "U1") (pin "8") (pinfunction "PH_8") (pintype "passive"))
    )
    (net (code "96") (name "Net-(LED1-A)") (class "Default")
      (node (ref "LED1") (pin "1") (pinfunction "A_1") (pintype "passive"))
      (node (ref "R7") (pin "2") (pinfunction "2_2") (pintype "passive"))
    )
    (net (code "97") (name "Net-(Q1-D)") (class "Default")
      (node (ref "Q1") (pin "3") (pinfunction "D_3") (pintype "passive"))
      (node (ref "R26") (pin "2") (pinfunction "2_2") (pintype "passive"))
    )
    (net (code "98") (name "Net-(Q1-G)") (class "Default")
      (node (ref "Q1") (pin "1") (pinfunction "G_1") (pintype "passive"))
      (node (ref "R8") (pin "1") (pinfunction "1_1") (pintype "passive"))
      (node (ref "R9") (pin "2") (pinfunction "2_2") (pintype "passive"))
    )
    (net (code "99") (name "Net-(Q2-D)") (class "Default")
      (node (ref "Q2") (pin "3") (pinfunction "D_3") (pintype "passive"))
      (node (ref "R25") (pin "2") (pinfunction "2_2") (pintype "passive"))
    )
    (net (code "100") (name "Net-(Q2-G)") (class "Default")
      (node (ref "Q2") (pin "1") (pinfunction "G_1") (pintype "passive"))
      (node (ref "R27") (pin "2") (pinfunction "2_2") (pintype "passive"))
      (node (ref "R28") (pin "1") (pinfunction "1_1") (pintype "passive"))
    )
    (net (code "101") (name "Net-(Q3-D)") (class "Default")
      (node (ref "Q3") (pin "3") (pinfunction "D_3") (pintype "passive"))
      (node (ref "R10") (pin "2") (pinfunction "2_2") (pintype "passive"))
    )
    (net (code "102") (name "Net-(Q3-G)") (class "Default")
      (node (ref "Q3") (pin "1") (pinfunction "G_1") (pintype "passive"))
      (node (ref "R29") (pin "1") (pinfunction "1_1") (pintype "passive"))
      (node (ref "R30") (pin "2") (pinfunction "2_2") (pintype "passive"))
    )
    (net (code "103") (name "Net-(Q4-G)") (class "Default")
      (node (ref "Q4") (pin "1") (pinfunction "G_1") (pintype "passive"))
      (node (ref "R64") (pin "2") (pinfunction "2_2") (pintype "passive"))
      (node (ref "R65") (pin "2") (pinfunction "2_2") (pintype "passive"))
    )
    (net (code "104") (name "Net-(R4-Pad2)") (class "Default")
      (node (ref "R4") (pin "2") (pinfunction "2_2") (pintype "passive"))
      (node (ref "R5") (pin "1") (pinfunction "1_1") (pintype "passive"))
      (node (ref "R6") (pin "1") (pinfunction "1_1") (pintype "passive"))
    )
    (net (code "105") (name "Net-(R55-Pad1)") (class "Default")
      (node (ref "R55") (pin "1") (pinfunction "1_1") (pintype "passive"))
      (node (ref "R59") (pin "2") (pinfunction "2_2") (pintype "passive"))
      (node (ref "S11") (pin "8") (pinfunction "8_8") (pintype "passive"))
    )
    (net (code "106") (name "Net-(R56-Pad1)") (class "Default")
      (node (ref "R56") (pin "1") (pinfunction "1_1") (pintype "passive"))
      (node (ref "R60") (pin "2") (pinfunction "2_2") (pintype "passive"))
      (node (ref "S11") (pin "7") (pinfunction "7_7") (pintype "passive"))
    )
    (net (code "107") (name "Net-(R57-Pad1)") (class "Default")
      (node (ref "R57") (pin "1") (pinfunction "1_1") (pintype "passive"))
      (node (ref "R61") (pin "2") (pinfunction "2_2") (pintype "passive"))
      (node (ref "S11") (pin "6") (pinfunction "6_6") (pintype "passive"))
    )
    (net (code "108") (name "Net-(R58-Pad1)") (class "Default")
      (node (ref "R58") (pin "1") (pinfunction "1_1") (pintype "passive"))
      (node (ref "R62") (pin "2") (pinfunction "2_2") (pintype "passive"))
      (node (ref "S11") (pin "5") (pinfunction "5_5") (pintype "passive"))
    )
    (net (code "109") (name "Net-(RGB-B)") (class "Default")
      (node (ref "R10") (pin "1") (pinfunction "1_1") (pintype "passive"))
      (node (ref "RGB") (pin "6") (pinfunction "B_6") (pintype "passive"))
    )
    (net (code "110") (name "Net-(RGB-G)") (class "Default")
      (node (ref "R26") (pin "1") (pinfunction "1_1") (pintype "passive"))
      (node (ref "RGB") (pin "2") (pinfunction "G_2") (pintype "passive"))
    )
    (net (code "111") (name "Net-(RGB-R)") (class "Default")
      (node (ref "R25") (pin "1") (pinfunction "1_1") (pintype "passive"))
      (node (ref "RGB") (pin "4") (pinfunction "R_4") (pintype "passive"))
    )
    (net (code "112") (name "Net-(U1-BOOT)") (class "Default")
      (node (ref "C1") (pin "1") (pinfunction "1_1") (pintype "passive"))
      (node (ref "U1") (pin "1") (pinfunction "BOOT_1") (pintype "passive"))
    )
    (net (code "113") (name "Net-(U1-VSENSE)") (class "Default")
      (node (ref "R2") (pin "2") (pinfunction "2_2") (pintype "passive"))
      (node (ref "R3") (pin "1") (pinfunction "1_1") (pintype "passive"))
      (node (ref "U1") (pin "4") (pinfunction "VSENSE_4") (pintype "passive"))
    )
    (net (code "114") (name "Net-(U11-BYP)") (class "Default")
      (node (ref "C2") (pin "2") (pinfunction "2_2") (pintype "passive"))
      (node (ref "U11") (pin "4") (pinfunction "BYP_4") (pintype "passive"))
    )
    (net (code "115") (name "Net-(U15-BOOT0{slash}VPP)") (class "Default")
      (node (ref "R19") (pin "2") (pinfunction "2_2") (pintype "passive"))
      (node (ref "U15") (pin "94") (pinfunction "BOOT0/VPP_94") (pintype "passive"))
    )
    (net (code "116") (name "Net-(U15-NRST)") (class "Default")
      (node (ref "C8") (pin "1") (pinfunction "1_1") (pintype "passive"))
      (node (ref "U15") (pin "14") (pinfunction "NRST_14") (pintype "passive"))
    )
    (net (code "117") (name "Net-(U15-PH0{slash}OSC_IN)") (class "Default")
      (node (ref "U15") (pin "12") (pinfunction "PH0/OSC_IN_12") (pintype "passive"))
      (node (ref "X1") (pin "3") (pinfunction "OSC2_3") (pintype "passive"))
    )
    (net (code "118") (name "Net-(U15-PH1{slash}OSC_OUT)") (class "Default")
      (node (ref "U15") (pin "13") (pinfunction "PH1/OSC_OUT_13") (pintype "passive"))
      (node (ref "X1") (pin "1") (pinfunction "OSC1_1") (pintype "passive"))
    )
    (net (code "119") (name "Net-(U15-VCAP1)") (class "Default")
      (node (ref "C6") (pin "2") (pinfunction "2_2") (pintype "passive"))
      (node (ref "U15") (pin "49") (pinfunction "VCAP1_49") (pintype "passive"))
    )
    (net (code "120") (name "Net-(U15-VCAP2)") (class "Default")
      (node (ref "C7") (pin "2") (pinfunction "2_2") (pintype "passive"))
      (node (ref "U15") (pin "73") (pinfunction "VCAP2_73") (pintype "passive"))
    )
    (net (code "121") (name "VCC_2S~6S") (class "Default")
      (node (ref "D2") (pin "1") (pinfunction "A_1") (pintype "passive"))
      (node (ref "R4") (pin "1") (pinfunction "1_1") (pintype "passive"))
      (node (ref "sh1.0-6p") (pin "1") (pinfunction "1_1") (pintype "passive"))
      (node (ref "sh1.0-6p") (pin "2") (pinfunction "2_2") (pintype "passive"))
      (node (ref "sh1.0-6p") (pin "3") (pinfunction "3_3") (pintype "passive"))
    )
    (net (code "122") (name "VCC_3.3V") (class "Default")
      (node (ref "C5") (pin "2") (pinfunction "2_2") (pintype "passive"))
      (node (ref "R20") (pin "2") (pinfunction "2_2") (pintype "passive"))
      (node (ref "R7") (pin "1") (pinfunction "1_1") (pintype "passive"))
      (node (ref "S11") (pin "1") (pinfunction "1_1") (pintype "passive"))
      (node (ref "S11") (pin "2") (pinfunction "2_2") (pintype "passive"))
      (node (ref "S11") (pin "3") (pinfunction "3_3") (pintype "passive"))
      (node (ref "S11") (pin "4") (pinfunction "4_4") (pintype "passive"))
      (node (ref "T4") (pin "1") (pinfunction "1_1") (pintype "passive"))
      (node (ref "U10") (pin "4") (pinfunction "4_4") (pintype "passive"))
      (node (ref "U11") (pin "5") (pinfunction "OUT_5") (pintype "passive"))
      (node (ref "U15") (pin "100") (pinfunction "VDD_3_100") (pintype "passive"))
      (node (ref "U15") (pin "11") (pinfunction "VDD_5_11") (pintype "passive"))
      (node (ref "U15") (pin "19") (pinfunction "VDD_19") (pintype "passive"))
      (node (ref "U15") (pin "21") (pinfunction "VREF+_21") (pintype "passive"))
      (node (ref "U15") (pin "22") (pinfunction "VDDA_22") (pintype "passive"))
      (node (ref "U15") (pin "28") (pinfunction "VDD_4_28") (pintype "passive"))
      (node (ref "U15") (pin "50") (pinfunction "VDD_1_50") (pintype "passive"))
      (node (ref "U15") (pin "6") (pinfunction "VBAT_6") (pintype "passive"))
      (node (ref "U15") (pin "75") (pinfunction "VDD_2_75") (pintype "passive"))
      (node (ref "W1") (pin "3") (pinfunction "/WP_3") (pintype "passive"))
      (node (ref "W1") (pin "7") (pinfunction "/HOLD_7") (pintype "passive"))
      (node (ref "W1") (pin "8") (pinfunction "VCC_8") (pintype "passive"))
    )
    (net (code "123") (name "VCC_5.0V") (class "Default")
      (node (ref "C3") (pin "2") (pinfunction "2_2") (pintype "passive"))
      (node (ref "C4") (pin "2") (pinfunction "2_2") (pintype "passive"))
      (node (ref "D1") (pin "2") (pinfunction "K_2") (pintype "passive"))
      (node (ref "H2") (pin "1") (pinfunction "1_1") (pintype "passive"))
      (node (ref "H2") (pin "2") (pinfunction "2_2") (pintype "passive"))
      (node (ref "H2") (pin "3") (pinfunction "3_3") (pintype "passive"))
      (node (ref "H2") (pin "4") (pinfunction "4_4") (pintype "passive"))
      (node (ref "H4") (pin "8") (pinfunction "8_8") (pintype "passive"))
      (node (ref "LX_IMU") (pin "2") (pinfunction "5V_2") (pintype "passive"))
      (node (ref "P1") (pin "2") (pinfunction "2_2") (pintype "passive"))
      (node (ref "P2_IMU") (pin "2") (pinfunction "5V_2") (pintype "passive"))
      (node (ref "R63") (pin "1") (pinfunction "1_1") (pintype "passive"))
      (node (ref "RGB") (pin "1") (pinfunction "VCC_1") (pintype "passive"))
      (node (ref "U11") (pin "1") (pinfunction "EN_1") (pintype "passive"))
      (node (ref "U11") (pin "3") (pinfunction "IN_3") (pintype "passive"))
      (node (ref "U16") (pin "1") (pinfunction "1_1") (pintype "passive"))
      (node (ref "U2") (pin "1") (pinfunction "VDD_1") (pintype "passive"))
      (node (ref "U3") (pin "1") (pinfunction "1_1") (pintype "passive"))
      (node (ref "U4") (pin "1") (pinfunction "1_1") (pintype "passive"))
      (node (ref "U5") (pin "1") (pinfunction "1_1") (pintype "passive"))
      (node (ref "U6") (pin "1") (pinfunction "1_1") (pintype "passive"))
      (node (ref "U7") (pin "1") (pinfunction "1_1") (pintype "passive"))
      (node (ref "U8") (pin "2") (pinfunction "2_2") (pintype "passive"))
      (node (ref "U9") (pin "2") (pinfunction "2_2") (pintype "passive"))
    )
    (net (code "124") (name "VCC_IN") (class "Default")
      (node (ref "D2") (pin "2") (pinfunction "K_2") (pintype "passive"))
      (node (ref "T1") (pin "1") (pinfunction "1_1") (pintype "passive"))
      (node (ref "U1") (pin "7") (pinfunction "VIN_7") (pintype "passive"))
    )
    (net (code "125") (name "unconnected-(U1-ENA-Pad5)") (class "Default")
      (node (ref "U1") (pin "5") (pinfunction "ENA_5") (pintype "passive"))
    )
    (net (code "126") (name "unconnected-(U1-NC-Pad2)") (class "Default")
      (node (ref "U1") (pin "2") (pinfunction "NC_2") (pintype "passive"))
    )
    (net (code "127") (name "unconnected-(U1-NC-Pad3)") (class "Default")
      (node (ref "U1") (pin "3") (pinfunction "NC_3") (pintype "passive"))
    )
    (net (code "128") (name "unconnected-(U2-NCC-Pad4)") (class "Default")
      (node (ref "U2") (pin "4") (pinfunction "NCC_4") (pintype "passive"))
    )
    (net (code "129") (name "unconnected-(U15-ETH_MDC{slash}ADC123_IN11{slash}PC1-Pad16)") (class "Default")
      (node (ref "U15") (pin "16") (pinfunction "ETH_MDC/ADC123_IN11/PC1_16") (pintype "passive"))
    )
    (net (code "130") (name "unconnected-(U15-ETH_RXD0{slash}ADC12_IN14{slash}PC4-Pad33)") (class "Default")
      (node (ref "U15") (pin "33") (pinfunction "ETH_RXD0/ADC12_IN14/PC4_33") (pintype "passive"))
    )
    (net (code "131") (name "unconnected-(U15-FSMC_A16{slash}USART3_CTS{slash}PD11-Pad58)") (class "Default")
      (node (ref "U15") (pin "58") (pinfunction "FSMC_A16/USART3_CTS/PD11_58") (pintype "passive"))
    )
    (net (code "132") (name "unconnected-(U15-FSMC_CLK{slash}USART2_CTS{slash}PD3-Pad84)") (class "Default")
      (node (ref "U15") (pin "84") (pinfunction "FSMC_CLK/USART2_CTS/PD3_84") (pintype "passive"))
    )
    (net (code "133") (name "unconnected-(U15-FSMC_D3{slash}CAN1_TX{slash}PD1-Pad82)") (class "Default")
      (node (ref "U15") (pin "82") (pinfunction "FSMC_D3/CAN1_TX/PD1_82") (pintype "passive"))
    )
    (net (code "134") (name "unconnected-(U15-FSMC_D4{slash}PE7-Pad38)") (class "Default")
      (node (ref "U15") (pin "38") (pinfunction "FSMC_D4/PE7_38") (pintype "passive"))
    )
    (net (code "135") (name "unconnected-(U15-FSMC_D5{slash}PE8-Pad39)") (class "Default")
      (node (ref "U15") (pin "39") (pinfunction "FSMC_D5/PE8_39") (pintype "passive"))
    )
    (net (code "136") (name "unconnected-(U15-FSMC_D7{slash}PE10-Pad41)") (class "Default")
      (node (ref "U15") (pin "41") (pinfunction "FSMC_D7/PE10_41") (pintype "passive"))
    )
    (net (code "137") (name "unconnected-(U15-FSMC_D9{slash}PE12-Pad43)") (class "Default")
      (node (ref "U15") (pin "43") (pinfunction "FSMC_D9/PE12_43") (pintype "passive"))
    )
    (net (code "138") (name "unconnected-(U15-FSMC_D12{slash}PE15-Pad46)") (class "Default")
      (node (ref "U15") (pin "46") (pinfunction "FSMC_D12/PE15_46") (pintype "passive"))
    )
    (net (code "139") (name "unconnected-(U15-FSMC_D13{slash}USART3_TX{slash}PD8-Pad55)") (class "Default")
      (node (ref "U15") (pin "55") (pinfunction "FSMC_D13/USART3_TX/PD8_55") (pintype "passive"))
    )
    (net (code "140") (name "unconnected-(U15-FSMC_D14{slash}USART3_RX{slash}PD9-Pad56)") (class "Default")
      (node (ref "U15") (pin "56") (pinfunction "FSMC_D14/USART3_RX/PD9_56") (pintype "passive"))
    )
    (net (code "141") (name "unconnected-(U15-FSMC_D15{slash}USART3_CK{slash}PD10_P_P-Pad57)") (class "Default")
      (node (ref "U15") (pin "57") (pinfunction "FSMC_D15/USART3_CK/PD10_P_P_57") (pintype "passive"))
    )
    (net (code "142") (name "unconnected-(U15-FSMC_NOE{slash}USART2_RTS{slash}PD4-Pad85)") (class "Default")
      (node (ref "U15") (pin "85") (pinfunction "FSMC_NOE/USART2_RTS/PD4_85") (pintype "passive"))
    )
    (net (code "143") (name "unconnected-(U15-I2S_CKIN{slash}MCO2{slash}SDIO_D1{slash}I2C3_SDA{slash}DCMI_D3{slash}PC9-Pad66)") (class "Default")
      (node (ref "U15") (pin "66") (pinfunction "I2S_CKIN/MCO2/SDIO_D1/I2C3_SDA/DCMI_D3/PC9_66") (pintype "passive"))
    )
    (net (code "144") (name "unconnected-(U15-OTG_HS_ULPI_STP{slash}EVENTOUT{slash}PC0-Pad15)") (class "Default")
      (node (ref "U15") (pin "15") (pinfunction "OTG_HS_ULPI_STP/EVENTOUT/PC0_15") (pintype "passive"))
    )
    (net (code "145") (name "unconnected-(U15-PA2{slash}USART2_TX{slash}ADC123_IN2{slash}ETH_MDIO-Pad25)") (class "Default")
      (node (ref "U15") (pin "25") (pinfunction "PA2/USART2_TX/ADC123_IN2/ETH_MDIO_25") (pintype "passive"))
    )
    (net (code "146") (name "unconnected-(U15-PA3{slash}USART2_RX{slash}OTG_HS_ULPI_D0{slash}ADC123_IN3-Pad26)") (class "Default")
      (node (ref "U15") (pin "26") (pinfunction "PA3/USART2_RX/OTG_HS_ULPI_D0/ADC123_IN3_26") (pintype "passive"))
    )
    (net (code "147") (name "unconnected-(U15-PA8{slash}MCO1{slash}I2C3_SCL{slash}OTG_FS_SOF-Pad67)") (class "Default")
      (node (ref "U15") (pin "67") (pinfunction "PA8/MCO1/I2C3_SCL/OTG_FS_SOF_67") (pintype "passive"))
    )
    (net (code "148") (name "unconnected-(U15-PA15{slash}JTDI{slash}I2S3_WS-Pad77)") (class "Default")
      (node (ref "U15") (pin "77") (pinfunction "PA15/JTDI/I2S3_WS_77") (pintype "passive"))
    )
    (net (code "149") (name "unconnected-(U15-PB3{slash}JTDO{slash}SPI3_SCK{slash}I2S3_CK{slash}SPI1_SCK-Pad89)") (class "Default")
      (node (ref "U15") (pin "89") (pinfunction "PB3/JTDO/SPI3_SCK/I2S3_CK/SPI1_SCK_89") (pintype "passive"))
    )
    (net (code "150") (name "unconnected-(U15-PB4{slash}JNTRST{slash}SPI3_MISO{slash}SPI1_MISO{slash}I2S3ext_SD-Pad90)") (class "Default")
      (node (ref "U15") (pin "90") (pinfunction "PB4/JNTRST/SPI3_MISO/SPI1_MISO/I2S3ext_SD_90") (pintype "passive"))
    )
    (net (code "151") (name "unconnected-(U15-PB5{slash}CAN2_RX{slash}OTG_HS_ULPI_D7{slash}DCMI_D10{slash}I2S3_SD-Pad91)") (class "Default")
      (node (ref "U15") (pin "91") (pinfunction "PB5/CAN2_RX/OTG_HS_ULPI_D7/DCMI_D10/I2S3_SD_91") (pintype "passive"))
    )
    (net (code "152") (name "unconnected-(U15-PB6{slash}I2C1_SCL{slash}CAN2_TX{slash}OTG_FS_INTN{slash}DCMI_D5{slash}USART1_TX_2_2-Pad92)") (class "Default")
      (node (ref "U15") (pin "92") (pinfunction "PB6/I2C1_SCL/CAN2_TX/OTG_FS_INTN/DCMI_D5/USART1_TX_2_2_92") (pintype "passive"))
    )
    (net (code "153") (name "unconnected-(U15-PB7{slash}I2C1_SDA{slash}FSMC_NL{slash}DCMI_VSYNC{slash}USART1_RX-Pad93)") (class "Default")
      (node (ref "U15") (pin "93") (pinfunction "PB7/I2C1_SDA/FSMC_NL/DCMI_VSYNC/USART1_RX_93") (pintype "passive"))
    )
    (net (code "154") (name "unconnected-(U15-PB9{slash}I2S2_WS{slash}OTG_FS_SDA{slash}SDIO_D5{slash}DCMI_D7{slash}I2C1_SDA{slash}CAN1_TX-Pad96)") (class "Default")
      (node (ref "U15") (pin "96") (pinfunction "PB9/I2S2_WS/OTG_FS_SDA/SDIO_D5/DCMI_D7/I2C1_SDA/CAN1_TX_96") (pintype "passive"))
    )
    (net (code "155") (name "unconnected-(U15-PC14-OSC32_IN-Pad8)") (class "Default")
      (node (ref "U15") (pin "8") (pinfunction "PC14-OSC32_IN_8") (pintype "passive"))
    )
    (net (code "156") (name "unconnected-(U15-PC15-OSC32_OUT-Pad9)") (class "Default")
      (node (ref "U15") (pin "9") (pinfunction "PC15-OSC32_OUT_9") (pintype "passive"))
    )
    (net (code "157") (name "unconnected-(U15-SDIO_D0{slash}DCMI_D2{slash}PC8-Pad65)") (class "Default")
      (node (ref "U15") (pin "65") (pinfunction "SDIO_D0/DCMI_D2/PC8_65") (pintype "passive"))
    )
    (net (code "158") (name "unconnected-(U15-SPI2_MISO{slash}OTG_HS_ULPI_DIR{slash}I2S2ext_SD{slash}ADC123_IN12{slash}PC2-Pad17)") (class "Default")
      (node (ref "U15") (pin "17") (pinfunction "SPI2_MISO/OTG_HS_ULPI_DIR/I2S2ext_SD/ADC123_IN12/PC2_17") (pintype "passive"))
    )
    (net (code "159") (name "unconnected-(U15-SPI2_MOSI{slash}I2S2_SD{slash}OTG_HS_ULPI_NXT{slash}ADC123_IN13{slash}PC3-Pad18)") (class "Default")
      (node (ref "U15") (pin "18") (pinfunction "SPI2_MOSI/I2S2_SD/OTG_HS_ULPI_NXT/ADC123_IN13/PC3_18") (pintype "passive"))
    )
    (net (code "160") (name "unconnected-(U15-TAMPER-RTC_AF1{slash}PC13-Pad7)") (class "Default")
      (node (ref "U15") (pin "7") (pinfunction "TAMPER-RTC_AF1/PC13_7") (pintype "passive"))
    )
  )
)
